# tissue_board_v2.net
KiCad netlist of a schematic drawn in EAGLE
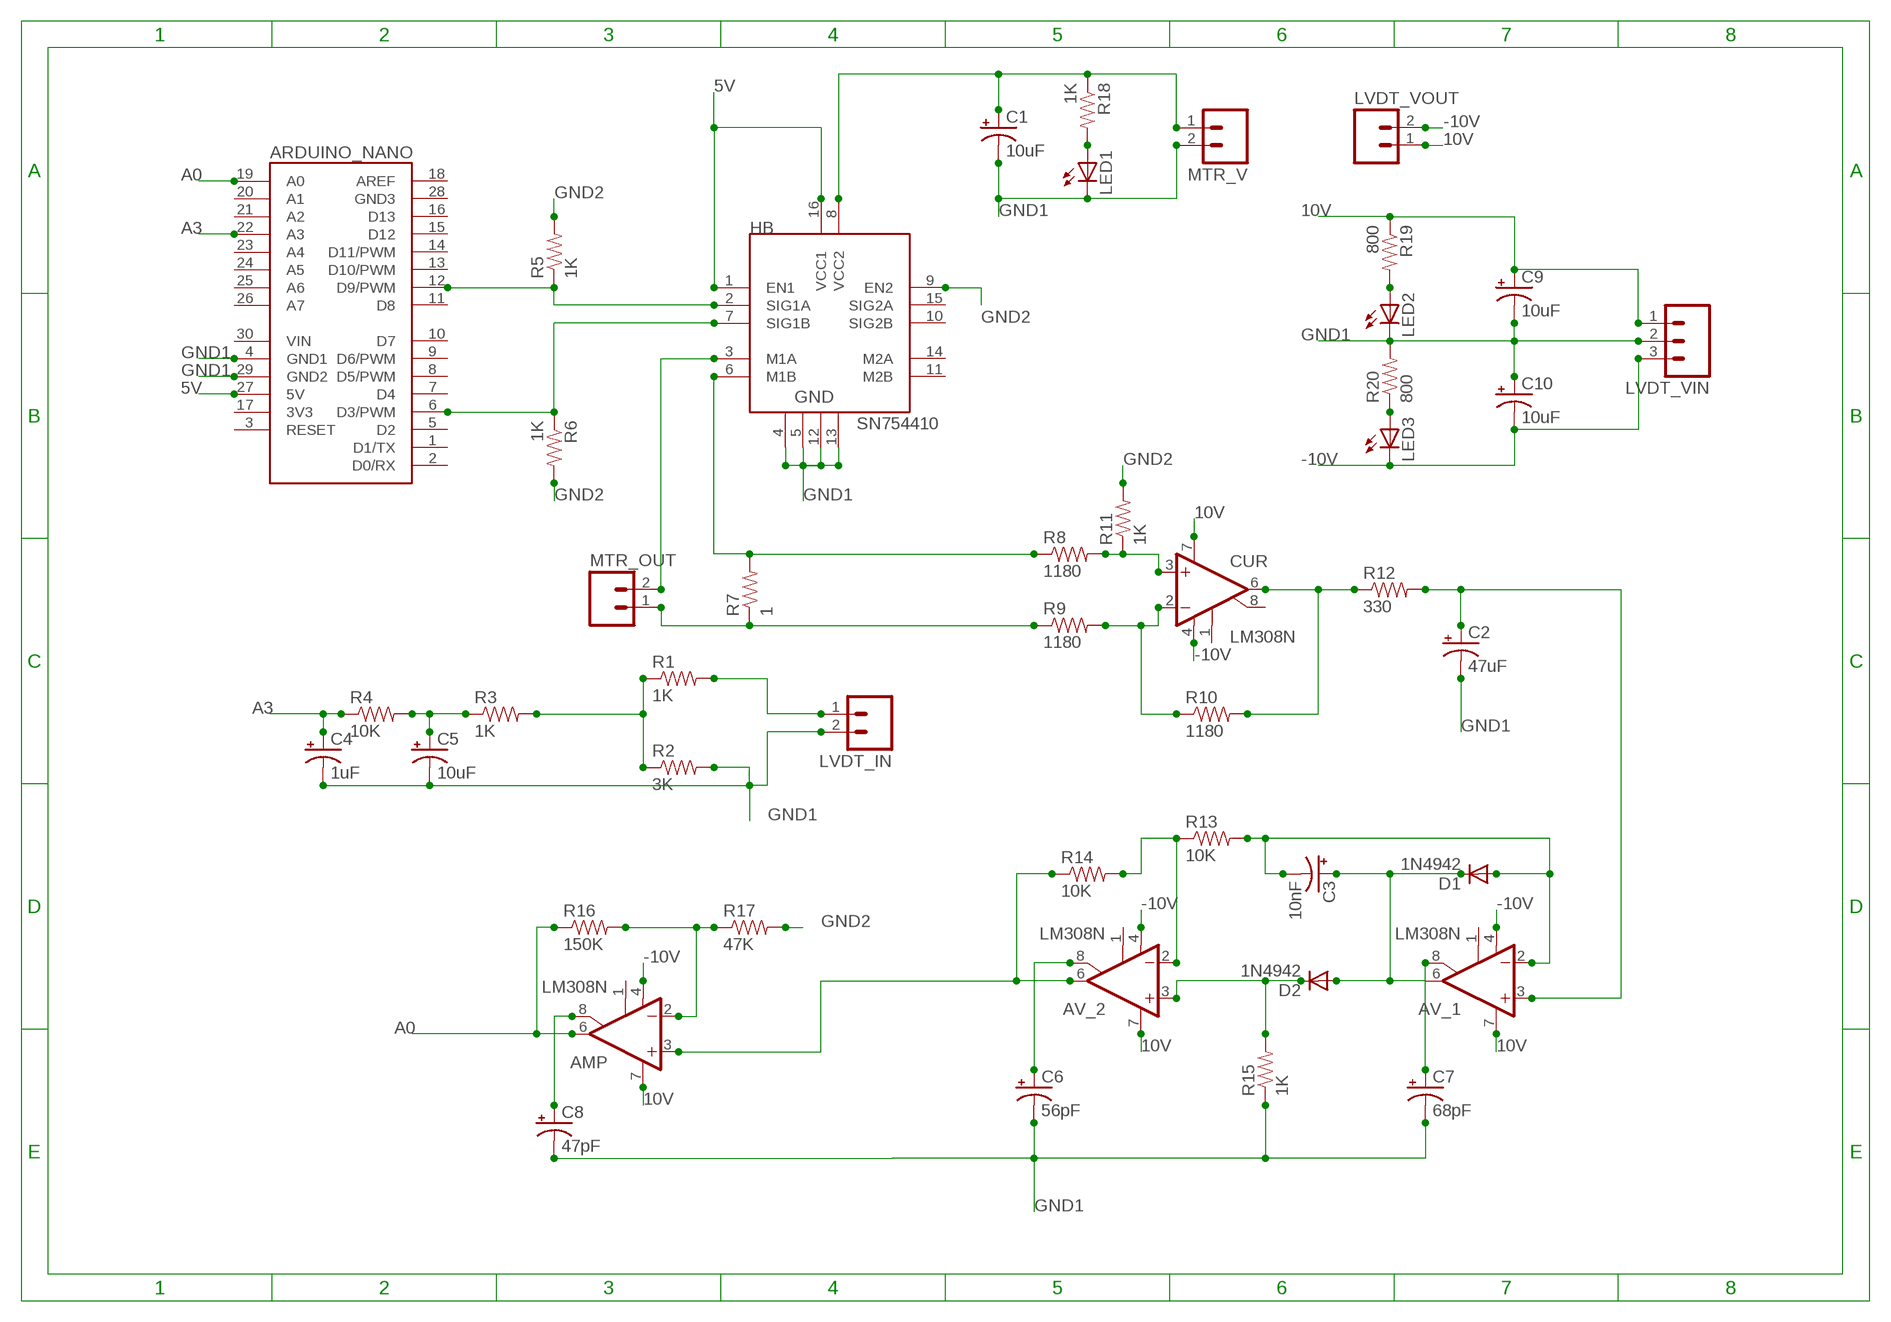
[diagram p0: schematic, sheet 1]

(export (version "E")
  (design (tool "Eeschema 10.0.6"))
  (components
    (comp (ref "AMP")
      (value "LM308N")
      (footprint "eagle-import:DIL08")
      (libsource (lib "eagle-import") (part "LM308N"))
    )
    (comp (ref "ARDUINO_NANO")
      (value "ARDUINO_NANO")
      (footprint "eagle-import:ARDUINO_NANO")
      (libsource (lib "eagle-import") (part "ARDUINO_NANO"))
    )
    (comp (ref "AV_1")
      (value "LM308N")
      (footprint "eagle-import:DIL08")
      (libsource (lib "eagle-import") (part "LM308N"))
    )
    (comp (ref "AV_2")
      (value "LM308N")
      (footprint "eagle-import:DIL08")
      (libsource (lib "eagle-import") (part "LM308N"))
    )
    (comp (ref "C1")
      (value "10uF")
      (footprint "eagle-import:CPOL-RADIAL-10UF-25V")
      (libsource (lib "eagle-import") (part "CAP_POLPTH2"))
    )
    (comp (ref "C2")
      (value "47uF")
      (footprint "eagle-import:CPOL-RADIAL-10UF-25V")
      (libsource (lib "eagle-import") (part "CAP_POLPTH2"))
    )
    (comp (ref "C3")
      (value "10nF")
      (footprint "eagle-import:CPOL-RADIAL-10UF-25V")
      (libsource (lib "eagle-import") (part "CAP_POLPTH2"))
    )
    (comp (ref "C4")
      (value "1uF")
      (footprint "eagle-import:CPOL-RADIAL-10UF-25V")
      (libsource (lib "eagle-import") (part "CAP_POLPTH2"))
    )
    (comp (ref "C5")
      (value "10uF")
      (footprint "eagle-import:CPOL-RADIAL-10UF-25V")
      (libsource (lib "eagle-import") (part "CAP_POLPTH2"))
    )
    (comp (ref "C6")
      (value "56pF")
      (footprint "eagle-import:CPOL-RADIAL-10UF-25V")
      (libsource (lib "eagle-import") (part "CAP_POLPTH2"))
    )
    (comp (ref "C7")
      (value "68pF")
      (footprint "eagle-import:CPOL-RADIAL-10UF-25V")
      (libsource (lib "eagle-import") (part "CAP_POLPTH2"))
    )
    (comp (ref "C8")
      (value "47pF")
      (footprint "eagle-import:CPOL-RADIAL-10UF-25V")
      (libsource (lib "eagle-import") (part "CAP_POLPTH2"))
    )
    (comp (ref "C9")
      (value "10uF")
      (footprint "eagle-import:CPOL-RADIAL-10UF-25V")
      (libsource (lib "eagle-import") (part "CAP_POLPTH2"))
    )
    (comp (ref "C10")
      (value "10uF")
      (footprint "eagle-import:CPOL-RADIAL-10UF-25V")
      (libsource (lib "eagle-import") (part "CAP_POLPTH2"))
    )
    (comp (ref "CUR")
      (value "LM308N")
      (footprint "eagle-import:DIL08")
      (libsource (lib "eagle-import") (part "LM308N"))
    )
    (comp (ref "D1")
      (value "1N4942")
      (footprint "eagle-import:DO41-10")
      (libsource (lib "eagle-import") (part "1N4942"))
    )
    (comp (ref "D2")
      (value "1N4942")
      (footprint "eagle-import:DO41-10")
      (libsource (lib "eagle-import") (part "1N4942"))
    )
    (comp (ref "HB")
      (value "SN754410")
      (footprint "eagle-import:DIP16")
      (libsource (lib "eagle-import") (part "SN754410"))
    )
    (comp (ref "LED1")
      (value "LED3MM")
      (footprint "eagle-import:LED3MM")
      (libsource (lib "eagle-import") (part "LED3MM"))
    )
    (comp (ref "LED2")
      (value "LED3MM")
      (footprint "eagle-import:LED3MM")
      (libsource (lib "eagle-import") (part "LED3MM"))
    )
    (comp (ref "LED3")
      (value "LED3MM")
      (footprint "eagle-import:LED3MM")
      (libsource (lib "eagle-import") (part "LED3MM"))
    )
    (comp (ref "LVDT_IN")
      (value "M023.5MM")
      (footprint "eagle-import:SCREWTERMINAL-3.5MM-2")
      (libsource (lib "eagle-import") (part "M023.5MM"))
    )
    (comp (ref "LVDT_VIN")
      (value "M03SCREW")
      (footprint "eagle-import:SCREWTERMINAL-3.5MM-3")
      (libsource (lib "eagle-import") (part "M03SCREW"))
    )
    (comp (ref "LVDT_VOUT")
      (value "M023.5MM")
      (footprint "eagle-import:SCREWTERMINAL-3.5MM-2")
      (libsource (lib "eagle-import") (part "M023.5MM"))
    )
    (comp (ref "MTR_OUT")
      (value "M023.5MM")
      (footprint "eagle-import:SCREWTERMINAL-3.5MM-2")
      (libsource (lib "eagle-import") (part "M023.5MM"))
    )
    (comp (ref "MTR_V")
      (value "M023.5MM")
      (footprint "eagle-import:SCREWTERMINAL-3.5MM-2")
      (libsource (lib "eagle-import") (part "M023.5MM"))
    )
    (comp (ref "R1")
      (value "1K")
      (footprint "eagle-import:AXIAL-0.4")
      (libsource (lib "eagle-import") (part "RESISTORPTH-1/4W"))
    )
    (comp (ref "R2")
      (value "3K")
      (footprint "eagle-import:AXIAL-0.4")
      (libsource (lib "eagle-import") (part "RESISTORPTH-1/4W"))
    )
    (comp (ref "R3")
      (value "1K")
      (footprint "eagle-import:AXIAL-0.4")
      (libsource (lib "eagle-import") (part "RESISTORPTH-1/4W"))
    )
    (comp (ref "R4")
      (value "10K")
      (footprint "eagle-import:AXIAL-0.4")
      (libsource (lib "eagle-import") (part "RESISTORPTH-1/4W"))
    )
    (comp (ref "R5")
      (value "1K")
      (footprint "eagle-import:AXIAL-0.4")
      (libsource (lib "eagle-import") (part "RESISTORPTH-1/4W"))
    )
    (comp (ref "R6")
      (value "1K")
      (footprint "eagle-import:AXIAL-0.4")
      (libsource (lib "eagle-import") (part "RESISTORPTH-1/4W"))
    )
    (comp (ref "R7")
      (value "1")
      (footprint "eagle-import:AXIAL-0.8")
      (libsource (lib "eagle-import") (part "RESISTORPTH-2W"))
    )
    (comp (ref "R8")
      (value "1180")
      (footprint "eagle-import:AXIAL-0.4")
      (libsource (lib "eagle-import") (part "RESISTORPTH-1/4W"))
    )
    (comp (ref "R9")
      (value "1180")
      (footprint "eagle-import:AXIAL-0.4")
      (libsource (lib "eagle-import") (part "RESISTORPTH-1/4W"))
    )
    (comp (ref "R10")
      (value "1180")
      (footprint "eagle-import:AXIAL-0.4")
      (libsource (lib "eagle-import") (part "RESISTORPTH-1/4W"))
    )
    (comp (ref "R11")
      (value "1K")
      (footprint "eagle-import:AXIAL-0.4")
      (libsource (lib "eagle-import") (part "RESISTORPTH-1/4W"))
    )
    (comp (ref "R12")
      (value "330")
      (footprint "eagle-import:AXIAL-0.4")
      (libsource (lib "eagle-import") (part "RESISTORPTH-1/4W"))
    )
    (comp (ref "R13")
      (value "10K")
      (footprint "eagle-import:AXIAL-0.4")
      (libsource (lib "eagle-import") (part "RESISTORPTH-1/4W"))
    )
    (comp (ref "R14")
      (value "10K")
      (footprint "eagle-import:AXIAL-0.4")
      (libsource (lib "eagle-import") (part "RESISTORPTH-1/4W"))
    )
    (comp (ref "R15")
      (value "1K")
      (footprint "eagle-import:AXIAL-0.4")
      (libsource (lib "eagle-import") (part "RESISTORPTH-1/4W"))
    )
    (comp (ref "R16")
      (value "150K")
      (footprint "eagle-import:AXIAL-0.4")
      (libsource (lib "eagle-import") (part "RESISTORPTH-1/4W"))
    )
    (comp (ref "R17")
      (value "47K")
      (footprint "eagle-import:AXIAL-0.4")
      (libsource (lib "eagle-import") (part "RESISTORPTH-1/4W"))
    )
    (comp (ref "R18")
      (value "1K")
      (footprint "eagle-import:AXIAL-0.4")
      (libsource (lib "eagle-import") (part "RESISTORPTH-1/4W"))
    )
    (comp (ref "R19")
      (value "800")
      (footprint "eagle-import:AXIAL-0.4")
      (libsource (lib "eagle-import") (part "RESISTORPTH-1/4W"))
    )
    (comp (ref "R20")
      (value "800")
      (footprint "eagle-import:AXIAL-0.4")
      (libsource (lib "eagle-import") (part "RESISTORPTH-1/4W"))
    )
  )
  (nets
    (net (code "1") (name "/-10V") (class "Default")
      (node (ref "AMP") (pin "4") (pinfunction "V-_4") (pintype "power_in"))
      (node (ref "AV_1") (pin "4") (pinfunction "V-_4") (pintype "power_in"))
      (node (ref "AV_2") (pin "4") (pinfunction "V-_4") (pintype "power_in"))
      (node (ref "C10") (pin "2") (pinfunction "-_2") (pintype "passive"))
      (node (ref "CUR") (pin "4") (pinfunction "V-_4") (pintype "power_in"))
      (node (ref "LED3") (pin "K") (pinfunction "C_K") (pintype "passive"))
      (node (ref "LVDT_VIN") (pin "3") (pinfunction "3_3") (pintype "passive"))
      (node (ref "LVDT_VOUT") (pin "2") (pinfunction "2_2") (pintype "passive"))
    )
    (net (code "2") (name "/3V3") (class "Default")
      (node (ref "ARDUINO_NANO") (pin "17") (pinfunction "3V3_17") (pintype "power_in"))
    )
    (net (code "3") (name "/5V") (class "Default")
      (node (ref "ARDUINO_NANO") (pin "27") (pinfunction "5V_27") (pintype "power_in"))
      (node (ref "HB") (pin "1") (pinfunction "EN1_1") (pintype "bidirectional"))
      (node (ref "HB") (pin "16") (pinfunction "VCC1_16") (pintype "power_in"))
    )
    (net (code "4") (name "/10V") (class "Default")
      (node (ref "AMP") (pin "7") (pinfunction "V+_7") (pintype "power_in"))
      (node (ref "AV_1") (pin "7") (pinfunction "V+_7") (pintype "power_in"))
      (node (ref "AV_2") (pin "7") (pinfunction "V+_7") (pintype "power_in"))
      (node (ref "C9") (pin "1") (pinfunction "+_1") (pintype "passive"))
      (node (ref "CUR") (pin "7") (pinfunction "V+_7") (pintype "power_in"))
      (node (ref "LVDT_VIN") (pin "1") (pinfunction "1_1") (pintype "passive"))
      (node (ref "LVDT_VOUT") (pin "1") (pinfunction "1_1") (pintype "passive"))
      (node (ref "R19") (pin "P$1") (pinfunction "1_P$1") (pintype "passive"))
    )
    (net (code "5") (name "/A0") (class "Default")
      (node (ref "AMP") (pin "6") (pinfunction "OUT_6") (pintype "output"))
      (node (ref "ARDUINO_NANO") (pin "19") (pinfunction "A0_19") (pintype "bidirectional"))
      (node (ref "R16") (pin "P$1") (pinfunction "1_P$1") (pintype "passive"))
    )
    (net (code "6") (name "/A3") (class "Default")
      (node (ref "ARDUINO_NANO") (pin "22") (pinfunction "A3_22") (pintype "bidirectional"))
      (node (ref "C4") (pin "1") (pinfunction "+_1") (pintype "passive"))
      (node (ref "R4") (pin "P$1") (pinfunction "1_P$1") (pintype "passive"))
    )
    (net (code "7") (name "/GND1") (class "Default")
      (node (ref "ARDUINO_NANO") (pin "29") (pinfunction "GND2_29") (pintype "power_in"))
      (node (ref "ARDUINO_NANO") (pin "4") (pinfunction "GND1_4") (pintype "power_in"))
      (node (ref "C1") (pin "2") (pinfunction "-_2") (pintype "passive"))
      (node (ref "C10") (pin "1") (pinfunction "+_1") (pintype "passive"))
      (node (ref "C2") (pin "2") (pinfunction "-_2") (pintype "passive"))
      (node (ref "C4") (pin "2") (pinfunction "-_2") (pintype "passive"))
      (node (ref "C5") (pin "2") (pinfunction "-_2") (pintype "passive"))
      (node (ref "C6") (pin "2") (pinfunction "-_2") (pintype "passive"))
      (node (ref "C7") (pin "2") (pinfunction "-_2") (pintype "passive"))
      (node (ref "C8") (pin "2") (pinfunction "-_2") (pintype "passive"))
      (node (ref "C9") (pin "2") (pinfunction "-_2") (pintype "passive"))
      (node (ref "HB") (pin "12") (pinfunction "P12_12") (pintype "power_in"))
      (node (ref "HB") (pin "13") (pinfunction "P13_13") (pintype "power_in"))
      (node (ref "HB") (pin "4") (pinfunction "P4_4") (pintype "power_in"))
      (node (ref "HB") (pin "5") (pinfunction "P5_5") (pintype "power_in"))
      (node (ref "LED1") (pin "K") (pinfunction "C_K") (pintype "passive"))
      (node (ref "LED2") (pin "K") (pinfunction "C_K") (pintype "passive"))
      (node (ref "LVDT_IN") (pin "2") (pinfunction "2_2") (pintype "passive"))
      (node (ref "LVDT_VIN") (pin "2") (pinfunction "2_2") (pintype "passive"))
      (node (ref "MTR_V") (pin "2") (pinfunction "2_2") (pintype "passive"))
      (node (ref "R15") (pin "P$1") (pinfunction "1_P$1") (pintype "passive"))
      (node (ref "R2") (pin "P$2") (pinfunction "2_P$2") (pintype "passive"))
      (node (ref "R20") (pin "P$2") (pinfunction "2_P$2") (pintype "passive"))
    )
    (net (code "8") (name "/GND2") (class "Default")
      (node (ref "HB") (pin "9") (pinfunction "EN2_9") (pintype "bidirectional"))
      (node (ref "R11") (pin "P$2") (pinfunction "2_P$2") (pintype "passive"))
      (node (ref "R17") (pin "P$2") (pinfunction "2_P$2") (pintype "passive"))
      (node (ref "R5") (pin "P$2") (pinfunction "2_P$2") (pintype "passive"))
      (node (ref "R6") (pin "P$2") (pinfunction "2_P$2") (pintype "passive"))
    )
    (net (code "9") (name "Net-(AMP-+IN)") (class "Default")
      (node (ref "AMP") (pin "3") (pinfunction "+IN_3") (pintype "input"))
      (node (ref "AV_2") (pin "6") (pinfunction "OUT_6") (pintype "output"))
      (node (ref "R14") (pin "P$1") (pinfunction "1_P$1") (pintype "passive"))
    )
    (net (code "10") (name "Net-(AMP--IN)") (class "Default")
      (node (ref "AMP") (pin "2") (pinfunction "-IN_2") (pintype "input"))
      (node (ref "R16") (pin "P$2") (pinfunction "2_P$2") (pintype "passive"))
      (node (ref "R17") (pin "P$1") (pinfunction "1_P$1") (pintype "passive"))
    )
    (net (code "11") (name "Net-(AMP-CMP2)") (class "Default")
      (node (ref "AMP") (pin "8") (pinfunction "CMP2_8") (pintype "passive"))
      (node (ref "C8") (pin "1") (pinfunction "+_1") (pintype "passive"))
    )
    (net (code "12") (name "Net-(ARDUINO_NANO-D3{slash}PWM)") (class "Default")
      (node (ref "ARDUINO_NANO") (pin "6") (pinfunction "D3/PWM_6") (pintype "bidirectional"))
      (node (ref "HB") (pin "7") (pinfunction "SIG1B_7") (pintype "bidirectional"))
      (node (ref "R6") (pin "P$1") (pinfunction "1_P$1") (pintype "passive"))
    )
    (net (code "13") (name "Net-(ARDUINO_NANO-D9{slash}PWM)") (class "Default")
      (node (ref "ARDUINO_NANO") (pin "12") (pinfunction "D9/PWM_12") (pintype "bidirectional"))
      (node (ref "HB") (pin "2") (pinfunction "SIG1A_2") (pintype "bidirectional"))
      (node (ref "R5") (pin "P$1") (pinfunction "1_P$1") (pintype "passive"))
    )
    (net (code "14") (name "Net-(AV_1-+IN)") (class "Default")
      (node (ref "AV_1") (pin "3") (pinfunction "+IN_3") (pintype "input"))
      (node (ref "C2") (pin "1") (pinfunction "+_1") (pintype "passive"))
      (node (ref "R12") (pin "P$2") (pinfunction "2_P$2") (pintype "passive"))
    )
    (net (code "15") (name "Net-(AV_1--IN)") (class "Default")
      (node (ref "AV_1") (pin "2") (pinfunction "-IN_2") (pintype "input"))
      (node (ref "C3") (pin "2") (pinfunction "-_2") (pintype "passive"))
      (node (ref "D1") (pin "A") (pinfunction "A_A") (pintype "passive"))
      (node (ref "R13") (pin "P$2") (pinfunction "2_P$2") (pintype "passive"))
    )
    (net (code "16") (name "Net-(AV_1-CMP2)") (class "Default")
      (node (ref "AV_1") (pin "8") (pinfunction "CMP2_8") (pintype "passive"))
      (node (ref "C7") (pin "1") (pinfunction "+_1") (pintype "passive"))
    )
    (net (code "17") (name "Net-(AV_1-OUT)") (class "Default")
      (node (ref "AV_1") (pin "6") (pinfunction "OUT_6") (pintype "output"))
      (node (ref "C3") (pin "1") (pinfunction "+_1") (pintype "passive"))
      (node (ref "D1") (pin "C") (pinfunction "C_C") (pintype "passive"))
      (node (ref "D2") (pin "A") (pinfunction "A_A") (pintype "passive"))
    )
    (net (code "18") (name "Net-(AV_2-+IN)") (class "Default")
      (node (ref "AV_2") (pin "3") (pinfunction "+IN_3") (pintype "input"))
      (node (ref "D2") (pin "C") (pinfunction "C_C") (pintype "passive"))
      (node (ref "R15") (pin "P$2") (pinfunction "2_P$2") (pintype "passive"))
    )
    (net (code "19") (name "Net-(AV_2--IN)") (class "Default")
      (node (ref "AV_2") (pin "2") (pinfunction "-IN_2") (pintype "input"))
      (node (ref "R13") (pin "P$1") (pinfunction "1_P$1") (pintype "passive"))
      (node (ref "R14") (pin "P$2") (pinfunction "2_P$2") (pintype "passive"))
    )
    (net (code "20") (name "Net-(AV_2-CMP2)") (class "Default")
      (node (ref "AV_2") (pin "8") (pinfunction "CMP2_8") (pintype "passive"))
      (node (ref "C6") (pin "1") (pinfunction "+_1") (pintype "passive"))
    )
    (net (code "21") (name "Net-(C1-+)") (class "Default")
      (node (ref "C1") (pin "1") (pinfunction "+_1") (pintype "passive"))
      (node (ref "HB") (pin "8") (pinfunction "VCC2_8") (pintype "power_in"))
      (node (ref "MTR_V") (pin "1") (pinfunction "1_1") (pintype "passive"))
      (node (ref "R18") (pin "P$1") (pinfunction "1_P$1") (pintype "passive"))
    )
    (net (code "22") (name "Net-(C5-+)") (class "Default")
      (node (ref "C5") (pin "1") (pinfunction "+_1") (pintype "passive"))
      (node (ref "R3") (pin "P$1") (pinfunction "1_P$1") (pintype "passive"))
      (node (ref "R4") (pin "P$2") (pinfunction "2_P$2") (pintype "passive"))
    )
    (net (code "23") (name "Net-(CUR-+IN)") (class "Default")
      (node (ref "CUR") (pin "3") (pinfunction "+IN_3") (pintype "input"))
      (node (ref "R11") (pin "P$1") (pinfunction "1_P$1") (pintype "passive"))
      (node (ref "R8") (pin "P$2") (pinfunction "2_P$2") (pintype "passive"))
    )
    (net (code "24") (name "Net-(CUR--IN)") (class "Default")
      (node (ref "CUR") (pin "2") (pinfunction "-IN_2") (pintype "input"))
      (node (ref "R10") (pin "P$1") (pinfunction "1_P$1") (pintype "passive"))
      (node (ref "R9") (pin "P$2") (pinfunction "2_P$2") (pintype "passive"))
    )
    (net (code "25") (name "Net-(CUR-OUT)") (class "Default")
      (node (ref "CUR") (pin "6") (pinfunction "OUT_6") (pintype "output"))
      (node (ref "R10") (pin "P$2") (pinfunction "2_P$2") (pintype "passive"))
      (node (ref "R12") (pin "P$1") (pinfunction "1_P$1") (pintype "passive"))
    )
    (net (code "26") (name "Net-(HB-M1A)") (class "Default")
      (node (ref "HB") (pin "3") (pinfunction "M1A_3") (pintype "bidirectional"))
      (node (ref "MTR_OUT") (pin "2") (pinfunction "2_2") (pintype "passive"))
    )
    (net (code "27") (name "Net-(HB-M1B)") (class "Default")
      (node (ref "HB") (pin "6") (pinfunction "M1B_6") (pintype "bidirectional"))
      (node (ref "R7") (pin "P$2") (pinfunction "2_P$2") (pintype "passive"))
      (node (ref "R8") (pin "P$1") (pinfunction "1_P$1") (pintype "passive"))
    )
    (net (code "28") (name "Net-(R1-1)") (class "Default")
      (node (ref "R1") (pin "P$1") (pinfunction "1_P$1") (pintype "passive"))
      (node (ref "R2") (pin "P$1") (pinfunction "1_P$1") (pintype "passive"))
      (node (ref "R3") (pin "P$2") (pinfunction "2_P$2") (pintype "passive"))
    )
    (net (code "29") (name "Net-(R1-2)") (class "Default")
      (node (ref "LVDT_IN") (pin "1") (pinfunction "1_1") (pintype "passive"))
      (node (ref "R1") (pin "P$2") (pinfunction "2_P$2") (pintype "passive"))
    )
    (net (code "30") (name "Net-(R7-1)") (class "Default")
      (node (ref "MTR_OUT") (pin "1") (pinfunction "1_1") (pintype "passive"))
      (node (ref "R7") (pin "P$1") (pinfunction "1_P$1") (pintype "passive"))
      (node (ref "R9") (pin "P$1") (pinfunction "1_P$1") (pintype "passive"))
    )
    (net (code "31") (name "Net-(R18-2)") (class "Default")
      (node (ref "LED1") (pin "A") (pinfunction "A_A") (pintype "passive"))
      (node (ref "R18") (pin "P$2") (pinfunction "2_P$2") (pintype "passive"))
    )
    (net (code "32") (name "Net-(R19-2)") (class "Default")
      (node (ref "LED2") (pin "A") (pinfunction "A_A") (pintype "passive"))
      (node (ref "R19") (pin "P$2") (pinfunction "2_P$2") (pintype "passive"))
    )
    (net (code "33") (name "Net-(R20-1)") (class "Default")
      (node (ref "LED3") (pin "A") (pinfunction "A_A") (pintype "passive"))
      (node (ref "R20") (pin "P$1") (pinfunction "1_P$1") (pintype "passive"))
    )
    (net (code "34") (name "unconnected-(AMP-CMP1-Pad1)") (class "Default")
      (node (ref "AMP") (pin "1") (pinfunction "CMP1_1") (pintype "passive"))
    )
    (net (code "35") (name "unconnected-(ARDUINO_NANO-A1-Pad20)") (class "Default")
      (node (ref "ARDUINO_NANO") (pin "20") (pinfunction "A1_20") (pintype "bidirectional"))
    )
    (net (code "36") (name "unconnected-(ARDUINO_NANO-A2-Pad21)") (class "Default")
      (node (ref "ARDUINO_NANO") (pin "21") (pinfunction "A2_21") (pintype "bidirectional"))
    )
    (net (code "37") (name "unconnected-(ARDUINO_NANO-A4-Pad23)") (class "Default")
      (node (ref "ARDUINO_NANO") (pin "23") (pinfunction "A4_23") (pintype "bidirectional"))
    )
    (net (code "38") (name "unconnected-(ARDUINO_NANO-A5-Pad24)") (class "Default")
      (node (ref "ARDUINO_NANO") (pin "24") (pinfunction "A5_24") (pintype "bidirectional"))
    )
    (net (code "39") (name "unconnected-(ARDUINO_NANO-A6-Pad25)") (class "Default")
      (node (ref "ARDUINO_NANO") (pin "25") (pinfunction "A6_25") (pintype "bidirectional"))
    )
    (net (code "40") (name "unconnected-(ARDUINO_NANO-A7-Pad26)") (class "Default")
      (node (ref "ARDUINO_NANO") (pin "26") (pinfunction "A7_26") (pintype "bidirectional"))
    )
    (net (code "41") (name "unconnected-(ARDUINO_NANO-AREF-Pad18)") (class "Default")
      (node (ref "ARDUINO_NANO") (pin "18") (pinfunction "AREF_18") (pintype "bidirectional"))
    )
    (net (code "42") (name "unconnected-(ARDUINO_NANO-D0{slash}RX-Pad2)") (class "Default")
      (node (ref "ARDUINO_NANO") (pin "2") (pinfunction "D0/RX_2") (pintype "bidirectional"))
    )
    (net (code "43") (name "unconnected-(ARDUINO_NANO-D1{slash}TX-Pad1)") (class "Default")
      (node (ref "ARDUINO_NANO") (pin "1") (pinfunction "D1/TX_1") (pintype "bidirectional"))
    )
    (net (code "44") (name "unconnected-(ARDUINO_NANO-D2-Pad5)") (class "Default")
      (node (ref "ARDUINO_NANO") (pin "5") (pinfunction "D2_5") (pintype "bidirectional"))
    )
    (net (code "45") (name "unconnected-(ARDUINO_NANO-D4-Pad7)") (class "Default")
      (node (ref "ARDUINO_NANO") (pin "7") (pinfunction "D4_7") (pintype "bidirectional"))
    )
    (net (code "46") (name "unconnected-(ARDUINO_NANO-D5{slash}PWM-Pad8)") (class "Default")
      (node (ref "ARDUINO_NANO") (pin "8") (pinfunction "D5/PWM_8") (pintype "bidirectional"))
    )
    (net (code "47") (name "unconnected-(ARDUINO_NANO-D6{slash}PWM-Pad9)") (class "Default")
      (node (ref "ARDUINO_NANO") (pin "9") (pinfunction "D6/PWM_9") (pintype "bidirectional"))
    )
    (net (code "48") (name "unconnected-(ARDUINO_NANO-D7-Pad10)") (class "Default")
      (node (ref "ARDUINO_NANO") (pin "10") (pinfunction "D7_10") (pintype "bidirectional"))
    )
    (net (code "49") (name "unconnected-(ARDUINO_NANO-D8-Pad11)") (class "Default")
      (node (ref "ARDUINO_NANO") (pin "11") (pinfunction "D8_11") (pintype "bidirectional"))
    )
    (net (code "50") (name "unconnected-(ARDUINO_NANO-D10{slash}PWM-Pad13)") (class "Default")
      (node (ref "ARDUINO_NANO") (pin "13") (pinfunction "D10/PWM_13") (pintype "bidirectional"))
    )
    (net (code "51") (name "unconnected-(ARDUINO_NANO-D11{slash}PWM-Pad14)") (class "Default")
      (node (ref "ARDUINO_NANO") (pin "14") (pinfunction "D11/PWM_14") (pintype "bidirectional"))
    )
    (net (code "52") (name "unconnected-(ARDUINO_NANO-D12-Pad15)") (class "Default")
      (node (ref "ARDUINO_NANO") (pin "15") (pinfunction "D12_15") (pintype "bidirectional"))
    )
    (net (code "53") (name "unconnected-(ARDUINO_NANO-D13-Pad16)") (class "Default")
      (node (ref "ARDUINO_NANO") (pin "16") (pinfunction "D13_16") (pintype "bidirectional"))
    )
    (net (code "54") (name "unconnected-(ARDUINO_NANO-GND3-Pad28)") (class "Default")
      (node (ref "ARDUINO_NANO") (pin "28") (pinfunction "GND3_28") (pintype "bidirectional"))
    )
    (net (code "55") (name "unconnected-(ARDUINO_NANO-RESET-Pad3)") (class "Default")
      (node (ref "ARDUINO_NANO") (pin "3") (pinfunction "RESET_3") (pintype "bidirectional"))
    )
    (net (code "56") (name "unconnected-(ARDUINO_NANO-VIN-Pad30)") (class "Default")
      (node (ref "ARDUINO_NANO") (pin "30") (pinfunction "VIN_30") (pintype "bidirectional"))
    )
    (net (code "57") (name "unconnected-(AV_1-CMP1-Pad1)") (class "Default")
      (node (ref "AV_1") (pin "1") (pinfunction "CMP1_1") (pintype "passive"))
    )
    (net (code "58") (name "unconnected-(AV_2-CMP1-Pad1)") (class "Default")
      (node (ref "AV_2") (pin "1") (pinfunction "CMP1_1") (pintype "passive"))
    )
    (net (code "59") (name "unconnected-(CUR-CMP1-Pad1)") (class "Default")
      (node (ref "CUR") (pin "1") (pinfunction "CMP1_1") (pintype "passive"))
    )
    (net (code "60") (name "unconnected-(CUR-CMP2-Pad8)") (class "Default")
      (node (ref "CUR") (pin "8") (pinfunction "CMP2_8") (pintype "passive"))
    )
    (net (code "61") (name "unconnected-(HB-M2A-Pad14)") (class "Default")
      (node (ref "HB") (pin "14") (pinfunction "M2A_14") (pintype "bidirectional"))
    )
    (net (code "62") (name "unconnected-(HB-M2B-Pad11)") (class "Default")
      (node (ref "HB") (pin "11") (pinfunction "M2B_11") (pintype "bidirectional"))
    )
    (net (code "63") (name "unconnected-(HB-SIG2A-Pad15)") (class "Default")
      (node (ref "HB") (pin "15") (pinfunction "SIG2A_15") (pintype "bidirectional"))
    )
    (net (code "64") (name "unconnected-(HB-SIG2B-Pad10)") (class "Default")
      (node (ref "HB") (pin "10") (pinfunction "SIG2B_10") (pintype "bidirectional"))
    )
  )
)
